# Clock_Generator_REV2.net
KiCad netlist of a schematic drawn in Altium Designer
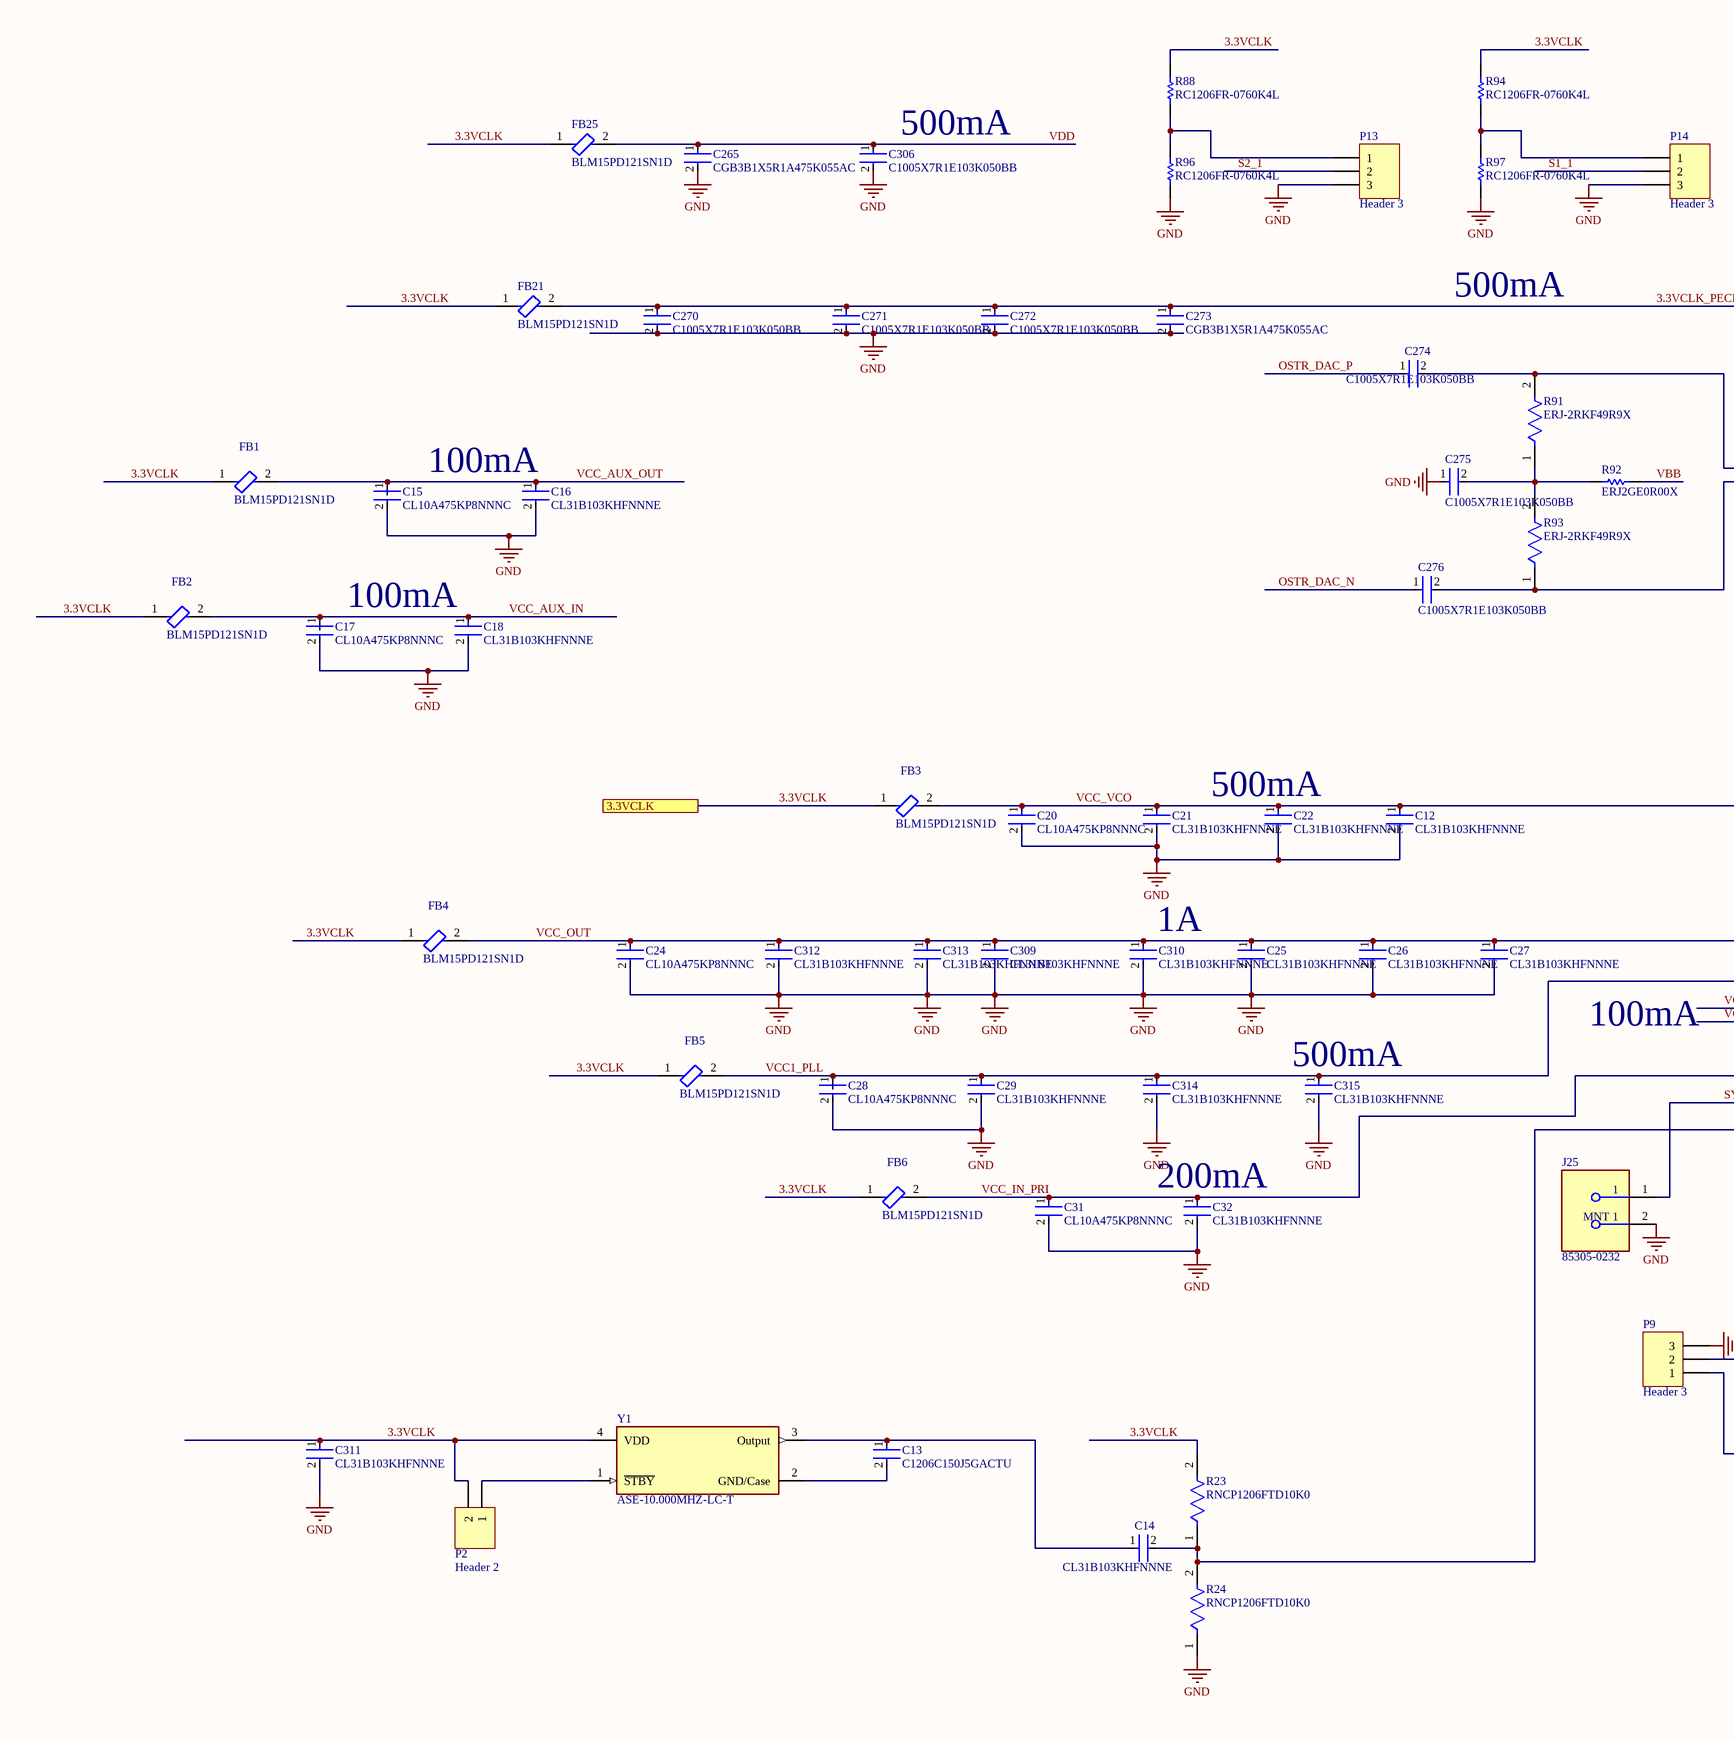
[diagram p0: Clock_Generator_REV2.SchDoc, left]
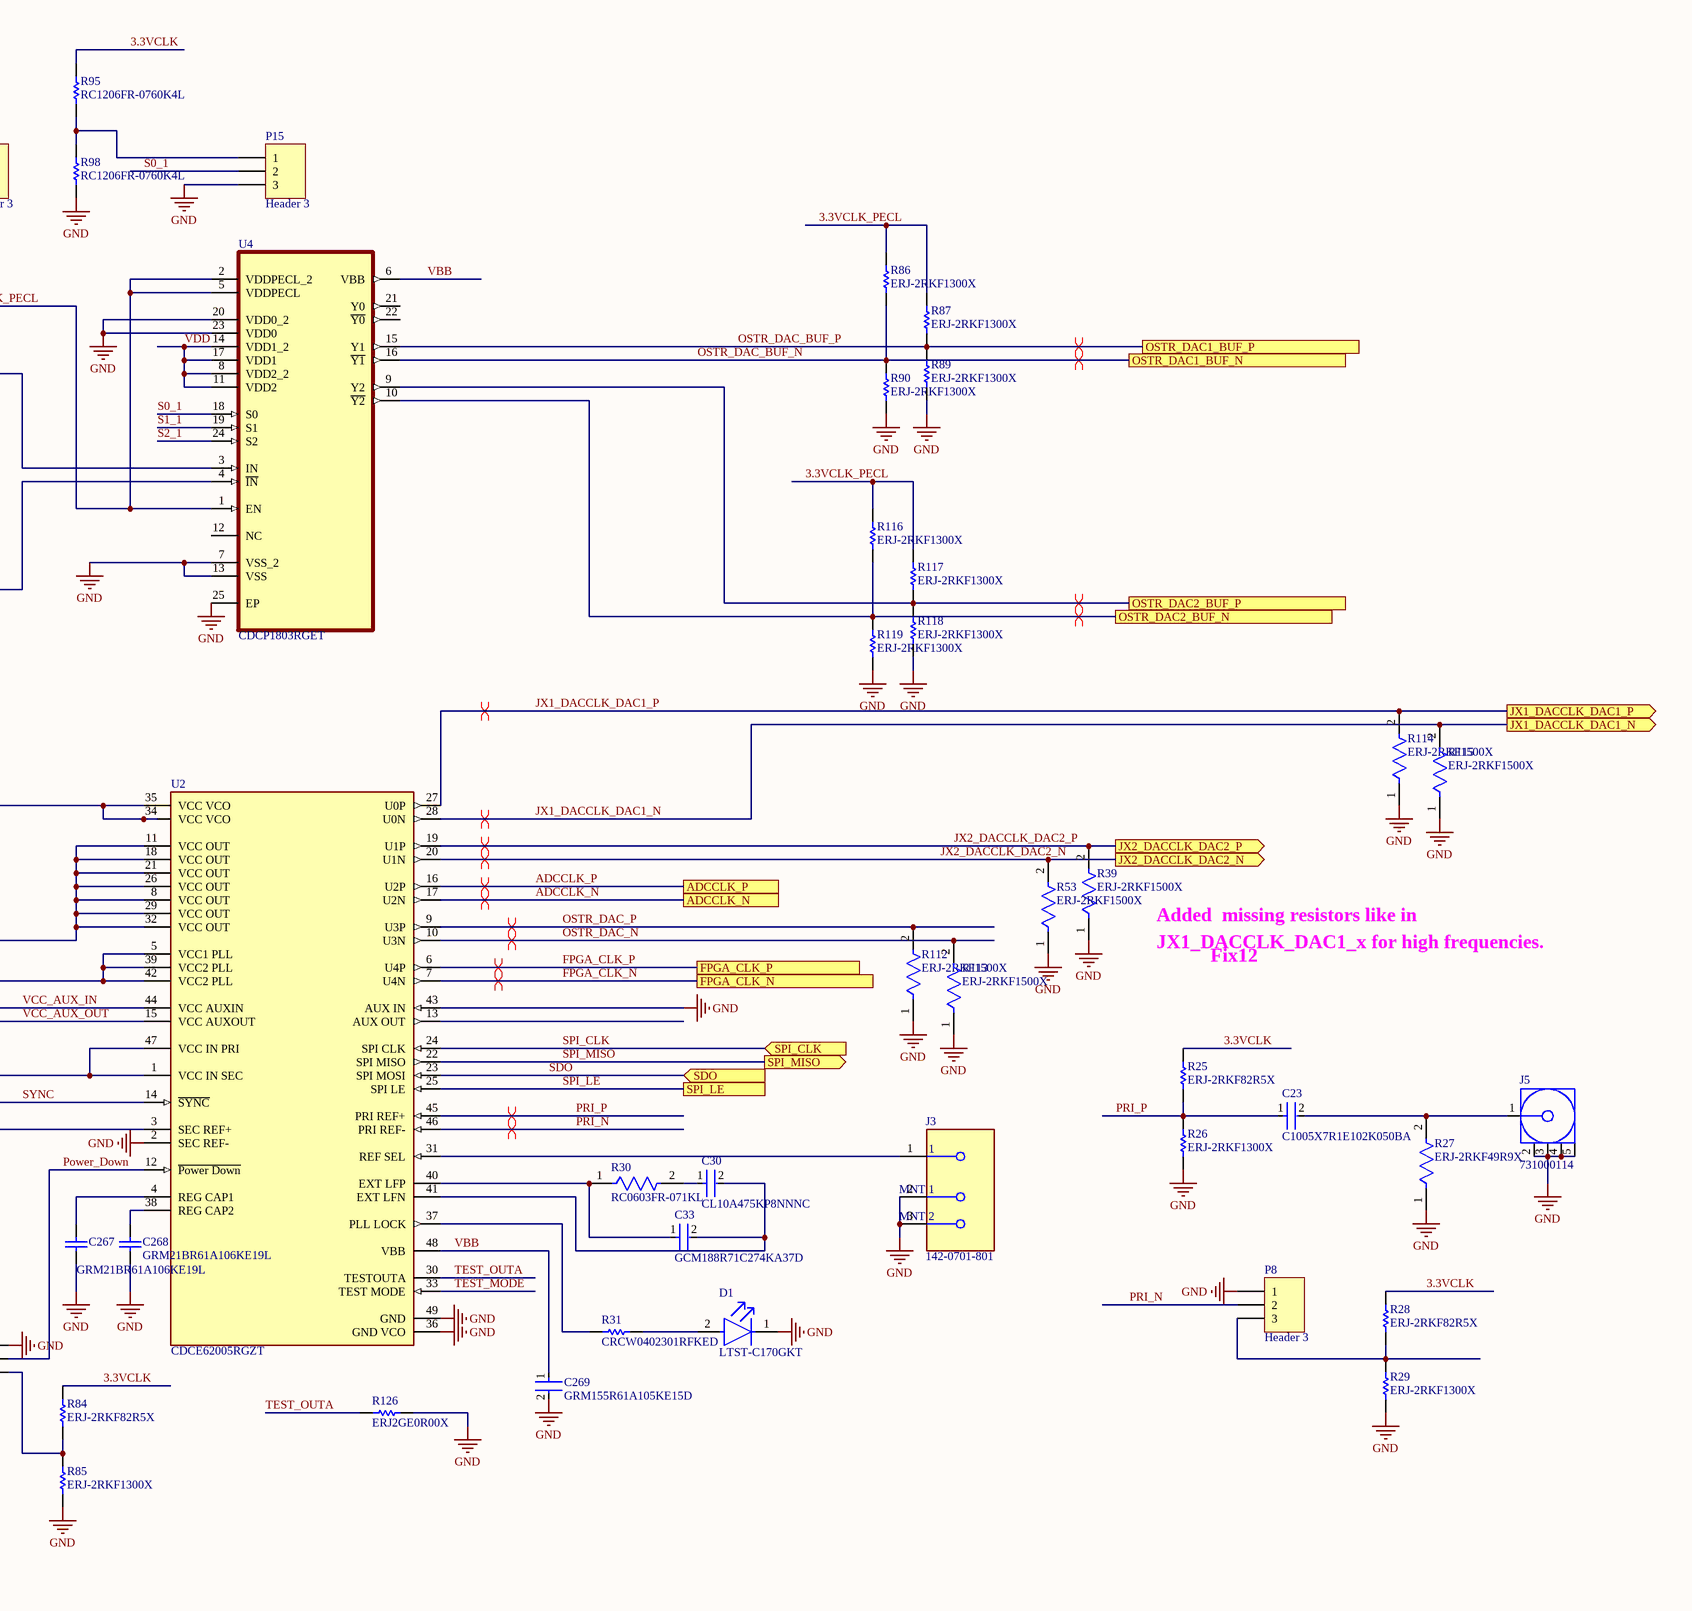
[diagram p1: Clock_Generator_REV2.SchDoc, right]

(export (version "E")
  (design (tool "Eeschema 10.0.6"))
  (components
    (comp (ref "C12")
      (value "CL31B103KHFNNNE")
      (footprint "C1206")
      (description "Cap Ceramic 10nF 630V X7R ±10% SMD 1206 +125°C Embossed T/R")
      (fields (field (name "TOLERANCE") "10%") (field (name "VOLTAGE") "630V"))
      (libsource (lib "DACֹֹ_Sources") (part "b4654b650e69147ec39a6b967a45e02"))
    )
    (comp (ref "C13")
      (value "C1206C150J5GACTU")
      (footprint "C1206")
      (description "1206 C 15pF Ceramic Multilayer Capacitor; 50 VDC; +125degC; C0G Dielec; +/-5%")
      (fields (field (name "TOLERANCE") "0.05") (field (name "MANUFACTURER") "KEMET"))
      (libsource (lib "DACֹֹ_Sources") (part "b4654b650e69147ec39a6b967a45e02"))
    )
    (comp (ref "C14")
      (value "CL31B103KHFNNNE")
      (footprint "C1206")
      (description "Cap Ceramic 10nF 630V X7R ±10% SMD 1206 +125°C Embossed T/R")
      (fields (field (name "TOLERANCE") "10%") (field (name "VOLTAGE") "630V"))
      (libsource (lib "DACֹֹ_Sources") (part "b4654b650e69147ec39a6b967a45e02"))
    )
    (comp (ref "C15")
      (value "CL10A475KP8NNNC")
      (footprint "C0603")
      (description "Cap Ceramic 4.7uF 10V X5R ±10% Pad SMD 0603 +85°C T/R")
      (fields (field (name "TOLERANCE") "10%"))
      (libsource (lib "DACֹֹ_Sources") (part "b4654b650e69147ec39a6b967a45e02"))
    )
    (comp (ref "C16")
      (value "CL31B103KHFNNNE")
      (footprint "C1206")
      (description "Cap Ceramic 10nF 630V X7R ±10% SMD 1206 +125°C Embossed T/R")
      (fields (field (name "TOLERANCE") "10%") (field (name "VOLTAGE") "630V"))
      (libsource (lib "DACֹֹ_Sources") (part "b4654b650e69147ec39a6b967a45e02"))
    )
    (comp (ref "C17")
      (value "CL10A475KP8NNNC")
      (footprint "C0603")
      (description "Cap Ceramic 4.7uF 10V X5R ±10% Pad SMD 0603 +85°C T/R")
      (fields (field (name "TOLERANCE") "10%"))
      (libsource (lib "DACֹֹ_Sources") (part "b4654b650e69147ec39a6b967a45e02"))
    )
    (comp (ref "C18")
      (value "CL31B103KHFNNNE")
      (footprint "C1206")
      (description "Cap Ceramic 10nF 630V X7R ±10% SMD 1206 +125°C Embossed T/R")
      (fields (field (name "TOLERANCE") "10%") (field (name "VOLTAGE") "630V"))
      (libsource (lib "DACֹֹ_Sources") (part "b4654b650e69147ec39a6b967a45e02"))
    )
    (comp (ref "C20")
      (value "CL10A475KP8NNNC")
      (footprint "C0603")
      (description "Cap Ceramic 4.7uF 10V X5R ±10% Pad SMD 0603 +85°C T/R")
      (fields (field (name "TOLERANCE") "10%"))
      (libsource (lib "DACֹֹ_Sources") (part "b4654b650e69147ec39a6b967a45e02"))
    )
    (comp (ref "C21")
      (value "CL31B103KHFNNNE")
      (footprint "C1206")
      (description "Cap Ceramic 10nF 630V X7R ±10% SMD 1206 +125°C Embossed T/R")
      (fields (field (name "TOLERANCE") "10%") (field (name "VOLTAGE") "630V"))
      (libsource (lib "DACֹֹ_Sources") (part "b4654b650e69147ec39a6b967a45e02"))
    )
    (comp (ref "C22")
      (value "CL31B103KHFNNNE")
      (footprint "C1206")
      (description "Cap Ceramic 10nF 630V X7R ±10% SMD 1206 +125°C Embossed T/R")
      (fields (field (name "TOLERANCE") "10%") (field (name "VOLTAGE") "630V"))
      (libsource (lib "DACֹֹ_Sources") (part "b4654b650e69147ec39a6b967a45e02"))
    )
    (comp (ref "C23")
      (value "C1005X7R1E102K050BA")
      (footprint "C0402")
      (description "Multilayer Ceramic Capacitors 1nF ±10% 25V X7R SMD 0402")
      (fields (field (name "TOLERANCE") "10%"))
      (libsource (lib "DACֹֹ_Sources") (part "b4654b650e69147ec39a6b967a45e02"))
    )
    (comp (ref "C24")
      (value "CL10A475KP8NNNC")
      (footprint "C0603")
      (description "Cap Ceramic 4.7uF 10V X5R ±10% Pad SMD 0603 +85°C T/R")
      (fields (field (name "TOLERANCE") "10%"))
      (libsource (lib "DACֹֹ_Sources") (part "b4654b650e69147ec39a6b967a45e02"))
    )
    (comp (ref "C25")
      (value "CL31B103KHFNNNE")
      (footprint "C1206")
      (description "Cap Ceramic 10nF 630V X7R ±10% SMD 1206 +125°C Embossed T/R")
      (fields (field (name "TOLERANCE") "10%") (field (name "VOLTAGE") "630V"))
      (libsource (lib "DACֹֹ_Sources") (part "b4654b650e69147ec39a6b967a45e02"))
    )
    (comp (ref "C26")
      (value "CL31B103KHFNNNE")
      (footprint "C1206")
      (description "Cap Ceramic 10nF 630V X7R ±10% SMD 1206 +125°C Embossed T/R")
      (fields (field (name "TOLERANCE") "10%") (field (name "VOLTAGE") "630V"))
      (libsource (lib "DACֹֹ_Sources") (part "b4654b650e69147ec39a6b967a45e02"))
    )
    (comp (ref "C27")
      (value "CL31B103KHFNNNE")
      (footprint "C1206")
      (description "Cap Ceramic 10nF 630V X7R ±10% SMD 1206 +125°C Embossed T/R")
      (fields (field (name "TOLERANCE") "10%") (field (name "VOLTAGE") "630V"))
      (libsource (lib "DACֹֹ_Sources") (part "b4654b650e69147ec39a6b967a45e02"))
    )
    (comp (ref "C28")
      (value "CL10A475KP8NNNC")
      (footprint "C0603")
      (description "Cap Ceramic 4.7uF 10V X5R ±10% Pad SMD 0603 +85°C T/R")
      (fields (field (name "TOLERANCE") "10%"))
      (libsource (lib "DACֹֹ_Sources") (part "b4654b650e69147ec39a6b967a45e02"))
    )
    (comp (ref "C29")
      (value "CL31B103KHFNNNE")
      (footprint "C1206")
      (description "Cap Ceramic 10nF 630V X7R ±10% SMD 1206 +125°C Embossed T/R")
      (fields (field (name "TOLERANCE") "10%") (field (name "VOLTAGE") "630V"))
      (libsource (lib "DACֹֹ_Sources") (part "b4654b650e69147ec39a6b967a45e02"))
    )
    (comp (ref "C30")
      (value "CL10A475KP8NNNC")
      (footprint "C0603")
      (description "Cap Ceramic 4.7uF 10V X5R ±10% Pad SMD 0603 +85°C T/R")
      (fields (field (name "TOLERANCE") "10%"))
      (libsource (lib "DACֹֹ_Sources") (part "b4654b650e69147ec39a6b967a45e02"))
    )
    (comp (ref "C31")
      (value "CL10A475KP8NNNC")
      (footprint "C0603")
      (description "Cap Ceramic 4.7uF 10V X5R ±10% Pad SMD 0603 +85°C T/R")
      (fields (field (name "TOLERANCE") "10%"))
      (libsource (lib "DACֹֹ_Sources") (part "b4654b650e69147ec39a6b967a45e02"))
    )
    (comp (ref "C32")
      (value "CL31B103KHFNNNE")
      (footprint "C1206")
      (description "Cap Ceramic 10nF 630V X7R ±10% SMD 1206 +125°C Embossed T/R")
      (fields (field (name "TOLERANCE") "10%") (field (name "VOLTAGE") "630V"))
      (libsource (lib "DACֹֹ_Sources") (part "b4654b650e69147ec39a6b967a45e02"))
    )
    (comp (ref "C33")
      (value "GCM188R71C274KA37D")
      (footprint "C0603")
      (description "Ceramic Capacitor for Automotive 270nF  ±10% 16VDC X7R 0603 Paper T/R")
      (fields (field (name "TOLERANCE") "10%"))
      (libsource (lib "DACֹֹ_Sources") (part "02cd4be3c70576c341d710602a673aa"))
    )
    (comp (ref "C265")
      (value "CGB3B1X5R1A475K055AC")
      (footprint "C0603")
      (description "CAP CER 4.7UF 10V X5R 0603")
      (fields (field (name "TOLERANCE") "10%"))
      (libsource (lib "DACֹֹ_Sources") (part "b4654b650e69147ec39a6b967a45e02"))
    )
    (comp (ref "C267")
      (value "GRM21BR61A106KE19L")
      (footprint "C0805")
      (description "CAP, Ceramic, 10 uF, 10%, 10 V, 0805, RoHS, Tape and Reel")
      (fields (field (name "MANUFACTURER") "Murata") (field (name "TOLERANCE") "±10%"))
      (libsource (lib "DACֹֹ_Sources") (part "CAP-NP-2"))
    )
    (comp (ref "C268")
      (value "GRM21BR61A106KE19L")
      (footprint "C0805")
      (description "CAP, Ceramic, 10 uF, 10%, 10 V, 0805, RoHS, Tape and Reel")
      (fields (field (name "MANUFACTURER") "Murata") (field (name "TOLERANCE") "±10%"))
      (libsource (lib "DACֹֹ_Sources") (part "CAP-NP-2"))
    )
    (comp (ref "C269")
      (value "GRM155R61A105KE15D")
      (footprint "C0402")
      (description "CAP CER 1UF 10V X5R 0402")
      (fields
        (field (name "OCTOPART") "https://octopart.com/grm155r61a105ke15d-murata-197442")
        (field (name "MANUFACTURER") "Murata")
      )
      (libsource (lib "DACֹֹ_Sources") (part "02cd4be3c70576c341d710602a673aa"))
    )
    (comp (ref "C270")
      (value "C1005X7R1E103K050BB")
      (footprint "C0402")
      (description "Multilayer Ceramic Capacitors 10nF ±10% 25V X7R SMD 0402")
      (fields (field (name "TOLERANCE") "10%") (field (name "VOLTAGE") "25V"))
      (libsource (lib "DACֹֹ_Sources") (part "b4654b650e69147ec39a6b967a45e02"))
    )
    (comp (ref "C271")
      (value "C1005X7R1E103K050BB")
      (footprint "C0402")
      (description "Multilayer Ceramic Capacitors 10nF ±10% 25V X7R SMD 0402")
      (fields (field (name "TOLERANCE") "10%") (field (name "VOLTAGE") "25V"))
      (libsource (lib "DACֹֹ_Sources") (part "b4654b650e69147ec39a6b967a45e02"))
    )
    (comp (ref "C272")
      (value "C1005X7R1E103K050BB")
      (footprint "C0402")
      (description "Multilayer Ceramic Capacitors 10nF ±10% 25V X7R SMD 0402")
      (fields (field (name "TOLERANCE") "10%") (field (name "VOLTAGE") "25V"))
      (libsource (lib "DACֹֹ_Sources") (part "b4654b650e69147ec39a6b967a45e02"))
    )
    (comp (ref "C273")
      (value "CGB3B1X5R1A475K055AC")
      (footprint "C0603")
      (description "CAP CER 4.7UF 10V X5R 0603")
      (fields (field (name "TOLERANCE") "10%"))
      (libsource (lib "DACֹֹ_Sources") (part "b4654b650e69147ec39a6b967a45e02"))
    )
    (comp (ref "C274")
      (value "C1005X7R1E103K050BB")
      (footprint "C0402")
      (description "Multilayer Ceramic Capacitors 10nF ±10% 25V X7R SMD 0402")
      (fields (field (name "TOLERANCE") "10%") (field (name "VOLTAGE") "25V"))
      (libsource (lib "DACֹֹ_Sources") (part "b4654b650e69147ec39a6b967a45e02"))
    )
    (comp (ref "C275")
      (value "C1005X7R1E103K050BB")
      (footprint "C0402")
      (description "Multilayer Ceramic Capacitors 10nF ±10% 25V X7R SMD 0402")
      (fields (field (name "TOLERANCE") "10%") (field (name "VOLTAGE") "25V"))
      (libsource (lib "DACֹֹ_Sources") (part "b4654b650e69147ec39a6b967a45e02"))
    )
    (comp (ref "C276")
      (value "C1005X7R1E103K050BB")
      (footprint "C0402")
      (description "Multilayer Ceramic Capacitors 10nF ±10% 25V X7R SMD 0402")
      (fields (field (name "TOLERANCE") "10%") (field (name "VOLTAGE") "25V"))
      (libsource (lib "DACֹֹ_Sources") (part "b4654b650e69147ec39a6b967a45e02"))
    )
    (comp (ref "C306")
      (value "C1005X7R1E103K050BB")
      (footprint "C0402")
      (description "Multilayer Ceramic Capacitors 10nF ±10% 25V X7R SMD 0402")
      (fields (field (name "TOLERANCE") "10%") (field (name "VOLTAGE") "25V"))
      (libsource (lib "DACֹֹ_Sources") (part "b4654b650e69147ec39a6b967a45e02"))
    )
    (comp (ref "C309")
      (value "CL31B103KHFNNNE")
      (footprint "C1206")
      (description "Cap Ceramic 10nF 630V X7R ±10% SMD 1206 +125°C Embossed T/R")
      (fields (field (name "TOLERANCE") "10%") (field (name "VOLTAGE") "630V"))
      (libsource (lib "DACֹֹ_Sources") (part "b4654b650e69147ec39a6b967a45e02"))
    )
    (comp (ref "C310")
      (value "CL31B103KHFNNNE")
      (footprint "C1206")
      (description "Cap Ceramic 10nF 630V X7R ±10% SMD 1206 +125°C Embossed T/R")
      (fields (field (name "TOLERANCE") "10%") (field (name "VOLTAGE") "630V"))
      (libsource (lib "DACֹֹ_Sources") (part "b4654b650e69147ec39a6b967a45e02"))
    )
    (comp (ref "C311")
      (value "CL31B103KHFNNNE")
      (footprint "C1206")
      (description "Cap Ceramic 10nF 630V X7R ±10% SMD 1206 +125°C Embossed T/R")
      (fields (field (name "TOLERANCE") "10%") (field (name "VOLTAGE") "630V"))
      (libsource (lib "DACֹֹ_Sources") (part "b4654b650e69147ec39a6b967a45e02"))
    )
    (comp (ref "C312")
      (value "CL31B103KHFNNNE")
      (footprint "C1206")
      (description "Cap Ceramic 10nF 630V X7R ±10% SMD 1206 +125°C Embossed T/R")
      (fields (field (name "TOLERANCE") "10%") (field (name "VOLTAGE") "630V"))
      (libsource (lib "DACֹֹ_Sources") (part "b4654b650e69147ec39a6b967a45e02"))
    )
    (comp (ref "C313")
      (value "CL31B103KHFNNNE")
      (footprint "C1206")
      (description "Cap Ceramic 10nF 630V X7R ±10% SMD 1206 +125°C Embossed T/R")
      (fields (field (name "TOLERANCE") "10%") (field (name "VOLTAGE") "630V"))
      (libsource (lib "DACֹֹ_Sources") (part "b4654b650e69147ec39a6b967a45e02"))
    )
    (comp (ref "C314")
      (value "CL31B103KHFNNNE")
      (footprint "C1206")
      (description "Cap Ceramic 10nF 630V X7R ±10% SMD 1206 +125°C Embossed T/R")
      (fields (field (name "TOLERANCE") "10%") (field (name "VOLTAGE") "630V"))
      (libsource (lib "DACֹֹ_Sources") (part "b4654b650e69147ec39a6b967a45e02"))
    )
    (comp (ref "C315")
      (value "CL31B103KHFNNNE")
      (footprint "C1206")
      (description "Cap Ceramic 10nF 630V X7R ±10% SMD 1206 +125°C Embossed T/R")
      (fields (field (name "TOLERANCE") "10%") (field (name "VOLTAGE") "630V"))
      (libsource (lib "DACֹֹ_Sources") (part "b4654b650e69147ec39a6b967a45e02"))
    )
    (comp (ref "D1")
      (value "LTST-C170GKT")
      (footprint "FP-LTST-C170GKT-MFG")
      (description "LED GREEN CLEAR SMD")
      (fields (field (name "VOLTAGE") "5V"))
      (libsource (lib "DACֹֹ_Sources") (part "8706943c75ba83719d021d2fdc84c58"))
    )
    (comp (ref "FB1")
      (value "BLM15PD121SN1D")
      (footprint "BLM15")
      (description "Chip Ferrite Bead, 0402, 120Ω @ 100MHz, 0.09Ω, 25%, 1.3A")
      (fields (field (name "TOLERANCE") "25%"))
      (libsource (lib "DACֹֹ_Sources") (part "5f30dd21d616792df468990f7003faa"))
    )
    (comp (ref "FB2")
      (value "BLM15PD121SN1D")
      (footprint "BLM15")
      (description "Chip Ferrite Bead, 0402, 120Ω @ 100MHz, 0.09Ω, 25%, 1.3A")
      (fields (field (name "TOLERANCE") "25%"))
      (libsource (lib "DACֹֹ_Sources") (part "5f30dd21d616792df468990f7003faa"))
    )
    (comp (ref "FB3")
      (value "BLM15PD121SN1D")
      (footprint "BLM15")
      (description "Chip Ferrite Bead, 0402, 120Ω @ 100MHz, 0.09Ω, 25%, 1.3A")
      (fields (field (name "TOLERANCE") "25%"))
      (libsource (lib "DACֹֹ_Sources") (part "5f30dd21d616792df468990f7003faa"))
    )
    (comp (ref "FB4")
      (value "BLM15PD121SN1D")
      (footprint "BLM15")
      (description "Chip Ferrite Bead, 0402, 120Ω @ 100MHz, 0.09Ω, 25%, 1.3A")
      (fields (field (name "TOLERANCE") "25%"))
      (libsource (lib "DACֹֹ_Sources") (part "5f30dd21d616792df468990f7003faa"))
    )
    (comp (ref "FB5")
      (value "BLM15PD121SN1D")
      (footprint "BLM15")
      (description "Chip Ferrite Bead, 0402, 120Ω @ 100MHz, 0.09Ω, 25%, 1.3A")
      (fields (field (name "TOLERANCE") "25%"))
      (libsource (lib "DACֹֹ_Sources") (part "5f30dd21d616792df468990f7003faa"))
    )
    (comp (ref "FB6")
      (value "BLM15PD121SN1D")
      (footprint "BLM15")
      (description "Chip Ferrite Bead, 0402, 120Ω @ 100MHz, 0.09Ω, 25%, 1.3A")
      (fields (field (name "TOLERANCE") "25%"))
      (libsource (lib "DACֹֹ_Sources") (part "5f30dd21d616792df468990f7003faa"))
    )
    (comp (ref "FB21")
      (value "BLM15PD121SN1D")
      (footprint "BLM15")
      (description "Chip Ferrite Bead, 0402, 120Ω @ 100MHz, 0.09Ω, 25%, 1.3A")
      (fields (field (name "TOLERANCE") "25%"))
      (libsource (lib "DACֹֹ_Sources") (part "5f30dd21d616792df468990f7003faa"))
    )
    (comp (ref "FB25")
      (value "BLM15PD121SN1D")
      (footprint "BLM15")
      (description "Chip Ferrite Bead, 0402, 120Ω @ 100MHz, 0.09Ω, 25%, 1.3A")
      (fields (field (name "TOLERANCE") "25%"))
      (libsource (lib "DACֹֹ_Sources") (part "5f30dd21d616792df468990f7003faa"))
    )
    (comp (ref "J3")
      (value "142-0701-801")
      (footprint "FP-142-0701-801-MFG")
      (description "CONN SMA JACK STR 50OHM EDGE MNT")
      (libsource (lib "DACֹֹ_Sources") (part "89929399afe843c8b6880c6cbd0f99a"))
    )
    (comp (ref "J5")
      (value "731000114")
      (footprint "MOLX-731000114_V")
      (description "SMA Right-Angle PCB Jack Receptacle, Brass Body, Gold Plated, 50 Ohm, 5-Pin THD, RoHS, Tray")
      (fields (field (name "MANUFACTURER") "Molex"))
      (libsource (lib "DACֹֹ_Sources") (part "CN-S-4F-RF5"))
    )
    (comp (ref "J25")
      (value "85305-0232")
      (footprint "FP-85305-0232-MFG")
      (description "CONN SMP PLUG STR 50 OHM SMD")
      (libsource (lib "DACֹֹ_Sources") (part "d2a53f3a980517e545f22a6fb6569cc"))
    )
    (comp (ref "P2")
      (value "Header 2")
      (footprint "HEADER_2X1")
      (description "Header, 2-Pin")
      (fields (field (name "PUBLISHER") "Altium Limited"))
      (libsource (lib "DACֹֹ_Sources") (part "Header 2"))
    )
    (comp (ref "P8")
      (value "Header 3")
      (footprint "HEADER_3X1")
      (description "Header, 3-Pin")
      (fields (field (name "PUBLISHER") "Altium Limited"))
      (libsource (lib "") (part "Header 3_1"))
    )
    (comp (ref "P9")
      (value "Header 3")
      (footprint "HEADER_3X1")
      (description "Header, 3-Pin")
      (fields (field (name "PUBLISHER") "Altium Limited"))
      (libsource (lib "DACֹֹ_Sources") (part "Header 3"))
    )
    (comp (ref "P13")
      (value "Header 3")
      (footprint "HEADER_3X1")
      (description "Header, 3-Pin")
      (fields (field (name "PUBLISHER") "Altium Limited"))
      (libsource (lib "") (part "Header 3_1"))
    )
    (comp (ref "P14")
      (value "Header 3")
      (footprint "HEADER_3X1")
      (description "Header, 3-Pin")
      (fields (field (name "PUBLISHER") "Altium Limited"))
      (libsource (lib "") (part "Header 3_1"))
    )
    (comp (ref "P15")
      (value "Header 3")
      (footprint "HEADER_3X1")
      (description "Header, 3-Pin")
      (fields (field (name "PUBLISHER") "Altium Limited"))
      (libsource (lib "") (part "Header 3_1"))
    )
    (comp (ref "R23")
      (value "RNCP1206FTD10K0")
      (footprint "R1206")
      (description "10kΩ ±1% 0.5W 1206 High Power Anti-Sulfur Thin Film Chip Resistor")
      (fields (field (name "TOLERANCE") "1%"))
      (libsource (lib "DACֹֹ_Sources") (part "1029c3af85768c4190bb7ad29bc67b5"))
    )
    (comp (ref "R24")
      (value "RNCP1206FTD10K0")
      (footprint "R1206")
      (description "10kΩ ±1% 0.5W 1206 High Power Anti-Sulfur Thin Film Chip Resistor")
      (fields (field (name "TOLERANCE") "1%"))
      (libsource (lib "DACֹֹ_Sources") (part "1029c3af85768c4190bb7ad29bc67b5"))
    )
    (comp (ref "R25")
      (value "ERJ-2RKF82R5X")
      (footprint "R0402")
      (fields (field (name "MANUFACTURER") "Panasonic"))
      (libsource (lib "DACֹֹ_Sources") (part "RES"))
    )
    (comp (ref "R26")
      (value "ERJ-2RKF1300X")
      (footprint "R0402")
      (fields (field (name "MANUFACTURER") "Panasonic"))
      (libsource (lib "DACֹֹ_Sources") (part "RES"))
    )
    (comp (ref "R27")
      (value "ERJ-2RKF49R9X")
      (footprint "R0402")
      (description "RES SMD 49.9 OHM 1% 1/10W 0402")
      (fields (field (name "TOLERANCE") "1%"))
      (libsource (lib "DACֹֹ_Sources") (part "8db39607336c341a927600551d01821"))
    )
    (comp (ref "R28")
      (value "ERJ-2RKF82R5X")
      (footprint "R0402")
      (fields (field (name "MANUFACTURER") "Panasonic"))
      (libsource (lib "DACֹֹ_Sources") (part "RES"))
    )
    (comp (ref "R29")
      (value "ERJ-2RKF1300X")
      (footprint "R0402")
      (fields (field (name "MANUFACTURER") "Panasonic"))
      (libsource (lib "DACֹֹ_Sources") (part "RES"))
    )
    (comp (ref "R30")
      (value "RC0603FR-071KL")
      (footprint "R0603")
      (description "RES 1K OHM 1% 1/10W 0603")
      (fields (field (name "TOLERANCE") "1%"))
      (libsource (lib "DACֹֹ_Sources") (part "1029c3af85768c4190bb7ad29bc67b5"))
    )
    (comp (ref "R31")
      (value "CRCW0402301RFKED")
      (footprint "R0402")
      (fields (field (name "MANUFACTURER") "Vishay Dale"))
      (libsource (lib "DACֹֹ_Sources") (part "RES"))
    )
    (comp (ref "R39")
      (value "ERJ-2RKF1500X")
      (footprint "R0402")
      (description "RES SMD 150 OHM 1% 1/10W 0402")
      (fields (field (name "TOLERANCE") "1%"))
      (libsource (lib "DACֹֹ_Sources") (part "1029c3af85768c4190bb7ad29bc67b5"))
    )
    (comp (ref "R53")
      (value "ERJ-2RKF1500X")
      (footprint "R0402")
      (description "RES SMD 150 OHM 1% 1/10W 0402")
      (fields (field (name "TOLERANCE") "1%"))
      (libsource (lib "DACֹֹ_Sources") (part "1029c3af85768c4190bb7ad29bc67b5"))
    )
    (comp (ref "R84")
      (value "ERJ-2RKF82R5X")
      (footprint "R0402")
      (fields (field (name "MANUFACTURER") "Panasonic"))
      (libsource (lib "DACֹֹ_Sources") (part "RES"))
    )
    (comp (ref "R85")
      (value "ERJ-2RKF1300X")
      (footprint "R0402")
      (fields (field (name "MANUFACTURER") "Panasonic"))
      (libsource (lib "DACֹֹ_Sources") (part "RES"))
    )
    (comp (ref "R86")
      (value "ERJ-2RKF1300X")
      (footprint "R0402")
      (fields (field (name "MANUFACTURER") "Panasonic"))
      (libsource (lib "DACֹֹ_Sources") (part "RES"))
    )
    (comp (ref "R87")
      (value "ERJ-2RKF1300X")
      (footprint "R0402")
      (fields (field (name "MANUFACTURER") "Panasonic"))
      (libsource (lib "DACֹֹ_Sources") (part "RES"))
    )
    (comp (ref "R88")
      (value "RC1206FR-0760K4L")
      (footprint "R1206")
      (fields (field (name "MANUFACTURER") "Yageo"))
      (libsource (lib "DACֹֹ_Sources") (part "RES"))
    )
    (comp (ref "R89")
      (value "ERJ-2RKF1300X")
      (footprint "R0402")
      (fields (field (name "MANUFACTURER") "Panasonic"))
      (libsource (lib "DACֹֹ_Sources") (part "RES"))
    )
    (comp (ref "R90")
      (value "ERJ-2RKF1300X")
      (footprint "R0402")
      (fields (field (name "MANUFACTURER") "Panasonic"))
      (libsource (lib "DACֹֹ_Sources") (part "RES"))
    )
    (comp (ref "R91")
      (value "ERJ-2RKF49R9X")
      (footprint "R0402")
      (description "RES SMD 49.9 OHM 1% 1/10W 0402")
      (fields (field (name "TOLERANCE") "1%"))
      (libsource (lib "DACֹֹ_Sources") (part "8db39607336c341a927600551d01821"))
    )
    (comp (ref "R92")
      (value "ERJ2GE0R00X")
      (footprint "R0402")
      (description "Chip Resistor, 0 Ohm, 0.1 W, -55 to 155 degC, 0402 (1005 Metric), RoHS, Tape and Reel")
      (fields (field (name "MANUFACTURER") "Panasonic") (field (name "TOLERANCE") "5%"))
      (libsource (lib "DACֹֹ_Sources") (part "RES-2"))
    )
    (comp (ref "R93")
      (value "ERJ-2RKF49R9X")
      (footprint "R0402")
      (description "RES SMD 49.9 OHM 1% 1/10W 0402")
      (fields (field (name "TOLERANCE") "1%"))
      (libsource (lib "DACֹֹ_Sources") (part "8db39607336c341a927600551d01821"))
    )
    (comp (ref "R94")
      (value "RC1206FR-0760K4L")
      (footprint "R1206")
      (fields (field (name "MANUFACTURER") "Yageo"))
      (libsource (lib "DACֹֹ_Sources") (part "RES"))
    )
    (comp (ref "R95")
      (value "RC1206FR-0760K4L")
      (footprint "R1206")
      (fields (field (name "MANUFACTURER") "Yageo"))
      (libsource (lib "DACֹֹ_Sources") (part "RES"))
    )
    (comp (ref "R96")
      (value "RC1206FR-0760K4L")
      (footprint "R1206")
      (fields (field (name "MANUFACTURER") "Yageo"))
      (libsource (lib "DACֹֹ_Sources") (part "RES"))
    )
    (comp (ref "R97")
      (value "RC1206FR-0760K4L")
      (footprint "R1206")
      (fields (field (name "MANUFACTURER") "Yageo"))
      (libsource (lib "DACֹֹ_Sources") (part "RES"))
    )
    (comp (ref "R98")
      (value "RC1206FR-0760K4L")
      (footprint "R1206")
      (fields (field (name "MANUFACTURER") "Yageo"))
      (libsource (lib "DACֹֹ_Sources") (part "RES"))
    )
    (comp (ref "R112")
      (value "ERJ-2RKF1500X")
      (footprint "R0402")
      (description "RES SMD 150 OHM 1% 1/10W 0402")
      (fields (field (name "TOLERANCE") "1%"))
      (libsource (lib "DACֹֹ_Sources") (part "1029c3af85768c4190bb7ad29bc67b5"))
    )
    (comp (ref "R113")
      (value "ERJ-2RKF1500X")
      (footprint "R0402")
      (description "RES SMD 150 OHM 1% 1/10W 0402")
      (fields (field (name "TOLERANCE") "1%"))
      (libsource (lib "DACֹֹ_Sources") (part "1029c3af85768c4190bb7ad29bc67b5"))
    )
    (comp (ref "R114")
      (value "ERJ-2RKF1500X")
      (footprint "R0402")
      (description "RES SMD 150 OHM 1% 1/10W 0402")
      (fields (field (name "TOLERANCE") "1%"))
      (libsource (lib "DACֹֹ_Sources") (part "1029c3af85768c4190bb7ad29bc67b5"))
    )
    (comp (ref "R115")
      (value "ERJ-2RKF1500X")
      (footprint "R0402")
      (description "RES SMD 150 OHM 1% 1/10W 0402")
      (fields (field (name "TOLERANCE") "1%"))
      (libsource (lib "DACֹֹ_Sources") (part "1029c3af85768c4190bb7ad29bc67b5"))
    )
    (comp (ref "R116")
      (value "ERJ-2RKF1300X")
      (footprint "R0402")
      (fields (field (name "MANUFACTURER") "Panasonic"))
      (libsource (lib "DACֹֹ_Sources") (part "RES"))
    )
    (comp (ref "R117")
      (value "ERJ-2RKF1300X")
      (footprint "R0402")
      (fields (field (name "MANUFACTURER") "Panasonic"))
      (libsource (lib "DACֹֹ_Sources") (part "RES"))
    )
    (comp (ref "R118")
      (value "ERJ-2RKF1300X")
      (footprint "R0402")
      (fields (field (name "MANUFACTURER") "Panasonic"))
      (libsource (lib "DACֹֹ_Sources") (part "RES"))
    )
    (comp (ref "R119")
      (value "ERJ-2RKF1300X")
      (footprint "R0402")
      (fields (field (name "MANUFACTURER") "Panasonic"))
      (libsource (lib "DACֹֹ_Sources") (part "RES"))
    )
    (comp (ref "R126")
      (value "ERJ2GE0R00X")
      (footprint "R0402")
      (description "Chip Resistor, 0 Ohm, 0.1 W, -55 to 155 degC, 0402 (1005 Metric), RoHS, Tape and Reel")
      (fields (field (name "MANUFACTURER") "Panasonic") (field (name "TOLERANCE") "5%"))
      (libsource (lib "DACֹֹ_Sources") (part "RES-2"))
    )
    (comp (ref "U2")
      (value "CDCE62005RGZT")
      (footprint "FP-RGZ0048D-IPC_A")
      (description "IC CLK SYNTH/JITTER CLEANR 48QFN")
      (libsource (lib "DACֹֹ_Sources") (part "79e6de338fe35b6fdc3d186d6aa1691"))
    )
    (comp (ref "U4")
      (value "CDCP1803RGET")
      (footprint "QFN25")
      (description "1:3 LVPECL clock buffer with programable divider")
      (fields (field (name "MF") "Texas Instruments"))
      (libsource (lib "DACֹֹ_Sources") (part "CDCP1803RGET"))
    )
    (comp (ref "Y1")
      (value "ASE-10.000MHZ-LC-T")
      (footprint "ASE")
      (description "XTAL Oscillator 10MHz ±50ppm CMOS 3.3V 4-SMD 3.2mm x 2.5mm")
      (libsource (lib "DACֹֹ_Sources") (part "61a724e6190563596ac712fef61ad37"))
    )
  )
  (nets
    (net (code "1") (name "/3.3VCLK") (class "Default")
      (node (ref "C311") (pin "1") (pinfunction "1_1") (pintype "passive"))
      (node (ref "FB1") (pin "1") (pinfunction "1_1") (pintype "passive"))
      (node (ref "FB2") (pin "1") (pinfunction "1_1") (pintype "passive"))
      (node (ref "FB21") (pin "1") (pinfunction "1_1") (pintype "passive"))
      (node (ref "FB25") (pin "1") (pinfunction "1_1") (pintype "passive"))
      (node (ref "FB3") (pin "1") (pinfunction "1_1") (pintype "passive"))
      (node (ref "FB4") (pin "1") (pinfunction "1_1") (pintype "passive"))
      (node (ref "FB5") (pin "1") (pinfunction "1_1") (pintype "passive"))
      (node (ref "FB6") (pin "1") (pinfunction "1_1") (pintype "passive"))
      (node (ref "P2") (pin "2") (pinfunction "2_2") (pintype "passive"))
      (node (ref "R23") (pin "2") (pinfunction "2_2") (pintype "passive"))
      (node (ref "R25") (pin "2") (pinfunction "2_2") (pintype "passive"))
      (node (ref "R28") (pin "2") (pinfunction "2_2") (pintype "passive"))
      (node (ref "R84") (pin "2") (pinfunction "2_2") (pintype "passive"))
      (node (ref "R88") (pin "2") (pinfunction "2_2") (pintype "passive"))
      (node (ref "R94") (pin "2") (pinfunction "2_2") (pintype "passive"))
      (node (ref "R95") (pin "2") (pinfunction "2_2") (pintype "passive"))
      (node (ref "Y1") (pin "4") (pinfunction "VDD_4") (pintype "power_in"))
    )
    (net (code "2") (name "/3.3VCLK_PECL") (class "Default")
      (node (ref "C270") (pin "1") (pinfunction "1_1") (pintype "passive"))
      (node (ref "C271") (pin "1") (pinfunction "1_1") (pintype "passive"))
      (node (ref "C272") (pin "1") (pinfunction "1_1") (pintype "passive"))
      (node (ref "C273") (pin "1") (pinfunction "1_1") (pintype "passive"))
      (node (ref "FB21") (pin "2") (pinfunction "2_2") (pintype "passive"))
      (node (ref "R116") (pin "2") (pinfunction "2_2") (pintype "passive"))
      (node (ref "R117") (pin "2") (pinfunction "2_2") (pintype "passive"))
      (node (ref "R86") (pin "2") (pinfunction "2_2") (pintype "passive"))
      (node (ref "R87") (pin "2") (pinfunction "2_2") (pintype "passive"))
      (node (ref "U4") (pin "1") (pinfunction "EN_1") (pintype "input"))
      (node (ref "U4") (pin "2") (pinfunction "VDDPECL_2_2") (pintype "power_in"))
      (node (ref "U4") (pin "5") (pinfunction "VDDPECL_5") (pintype "power_in"))
    )
    (net (code "3") (name "/ADCCLK_N") (class "Default")
      (node (ref "U2") (pin "17") (pinfunction "U2N_17") (pintype "output"))
    )
    (net (code "4") (name "/ADCCLK_P") (class "Default")
      (node (ref "U2") (pin "16") (pinfunction "U2P_16") (pintype "output"))
    )
    (net (code "5") (name "/FPGA_CLK_N") (class "Default")
      (node (ref "U2") (pin "7") (pinfunction "U4N_7") (pintype "output"))
    )
    (net (code "6") (name "/FPGA_CLK_P") (class "Default")
      (node (ref "U2") (pin "6") (pinfunction "U4P_6") (pintype "output"))
    )
    (net (code "7") (name "/JX1_DACCLK_DAC1_N") (class "Default")
      (node (ref "R115") (pin "2") (pinfunction "2_2") (pintype "passive"))
      (node (ref "U2") (pin "28") (pinfunction "U0N_28") (pintype "output"))
    )
    (net (code "8") (name "/JX1_DACCLK_DAC1_P") (class "Default")
      (node (ref "R114") (pin "2") (pinfunction "2_2") (pintype "passive"))
      (node (ref "U2") (pin "27") (pinfunction "U0P_27") (pintype "output"))
    )
    (net (code "9") (name "/JX2_DACCLK_DAC2_N") (class "Default")
      (node (ref "R53") (pin "2") (pinfunction "2_2") (pintype "passive"))
      (node (ref "U2") (pin "20") (pinfunction "U1N_20") (pintype "output"))
    )
    (net (code "10") (name "/JX2_DACCLK_DAC2_P") (class "Default")
      (node (ref "R39") (pin "2") (pinfunction "2_2") (pintype "passive"))
      (node (ref "U2") (pin "19") (pinfunction "U1P_19") (pintype "output"))
    )
    (net (code "11") (name "/OSTR_DAC2_BUF_N") (class "Default")
      (node (ref "R116") (pin "1") (pinfunction "1_1") (pintype "passive"))
      (node (ref "R119") (pin "2") (pinfunction "2_2") (pintype "passive"))
      (node (ref "U4") (pin "10") (pinfunction "~{Y2}_10") (pintype "output"))
    )
    (net (code "12") (name "/OSTR_DAC2_BUF_P") (class "Default")
      (node (ref "R117") (pin "1") (pinfunction "1_1") (pintype "passive"))
      (node (ref "R118") (pin "2") (pinfunction "2_2") (pintype "passive"))
      (node (ref "U4") (pin "9") (pinfunction "Y2_9") (pintype "output"))
    )
    (net (code "13") (name "/OSTR_DAC_BUF_N") (class "Default")
      (node (ref "R86") (pin "1") (pinfunction "1_1") (pintype "passive"))
      (node (ref "R90") (pin "2") (pinfunction "2_2") (pintype "passive"))
      (node (ref "U4") (pin "16") (pinfunction "~{Y1}_16") (pintype "output"))
    )
    (net (code "14") (name "/OSTR_DAC_BUF_P") (class "Default")
      (node (ref "R87") (pin "1") (pinfunction "1_1") (pintype "passive"))
      (node (ref "R89") (pin "2") (pinfunction "2_2") (pintype "passive"))
      (node (ref "U4") (pin "15") (pinfunction "Y1_15") (pintype "output"))
    )
    (net (code "15") (name "/OSTR_DAC_N") (class "Default")
      (node (ref "C276") (pin "1") (pinfunction "1_1") (pintype "passive"))
      (node (ref "R113") (pin "2") (pinfunction "2_2") (pintype "passive"))
      (node (ref "U2") (pin "10") (pinfunction "U3N_10") (pintype "output"))
    )
    (net (code "16") (name "/OSTR_DAC_P") (class "Default")
      (node (ref "C274") (pin "1") (pinfunction "1_1") (pintype "passive"))
      (node (ref "R112") (pin "2") (pinfunction "2_2") (pintype "passive"))
      (node (ref "U2") (pin "9") (pinfunction "U3P_9") (pintype "output"))
    )
    (net (code "17") (name "/PRI_N") (class "Default")
      (node (ref "P8") (pin "2") (pinfunction "2_2") (pintype "passive"))
      (node (ref "U2") (pin "46") (pinfunction "PRI_REF-_46") (pintype "input"))
    )
    (net (code "18") (name "/PRI_P") (class "Default")
      (node (ref "C23") (pin "1") (pinfunction "1_1") (pintype "passive"))
      (node (ref "R25") (pin "1") (pinfunction "1_1") (pintype "passive"))
      (node (ref "R26") (pin "2") (pinfunction "2_2") (pintype "passive"))
      (node (ref "U2") (pin "45") (pinfunction "PRI_REF+_45") (pintype "input"))
    )
    (net (code "19") (name "/Power_Down") (class "Default")
      (node (ref "P9") (pin "2") (pinfunction "2_2") (pintype "passive"))
      (node (ref "U2") (pin "12") (pinfunction "~{Power_Down}_12") (pintype "input"))
    )
    (net (code "20") (name "/S0_1") (class "Default")
      (node (ref "P15") (pin "2") (pinfunction "2_2") (pintype "passive"))
      (node (ref "U4") (pin "18") (pinfunction "S0_18") (pintype "input"))
    )
    (net (code "21") (name "/S1_1") (class "Default")
      (node (ref "P14") (pin "2") (pinfunction "2_2") (pintype "passive"))
      (node (ref "U4") (pin "19") (pinfunction "S1_19") (pintype "input"))
    )
    (net (code "22") (name "/S2_1") (class "Default")
      (node (ref "P13") (pin "2") (pinfunction "2_2") (pintype "passive"))
      (node (ref "U4") (pin "24") (pinfunction "S2_24") (pintype "input"))
    )
    (net (code "23") (name "/SDO") (class "Default")
      (node (ref "U2") (pin "23") (pinfunction "SPI_MOSI_23") (pintype "input"))
    )
    (net (code "24") (name "/SPI_CLK") (class "Default")
      (node (ref "U2") (pin "24") (pinfunction "SPI_CLK_24") (pintype "input"))
    )
    (net (code "25") (name "/SPI_LE") (class "Default")
      (node (ref "U2") (pin "25") (pinfunction "SPI_LE_25") (pintype "input"))
    )
    (net (code "26") (name "/SPI_MISO") (class "Default")
      (node (ref "U2") (pin "22") (pinfunction "SPI_MISO_22") (pintype "output"))
    )
    (net (code "27") (name "/SYNC") (class "Default")
      (node (ref "J25") (pin "1") (pinfunction "1_1") (pintype "passive"))
      (node (ref "U2") (pin "14") (pinfunction "~{SYNC}_14") (pintype "input"))
    )
    (net (code "28") (name "/TEST_MODE") (class "Default")
      (node (ref "U2") (pin "33") (pinfunction "TEST_MODE_33") (pintype "input"))
    )
    (net (code "29") (name "/TEST_OUTA") (class "Default")
      (node (ref "R126") (pin "1") (pinfunction "1_1") (pintype "passive"))
      (node (ref "U2") (pin "30") (pinfunction "TESTOUTA_30") (pintype "passive"))
    )
    (net (code "30") (name "/VBB") (class "Default")
      (node (ref "C269") (pin "1") (pinfunction "1_1") (pintype "passive"))
      (node (ref "R92") (pin "2") (pinfunction "2_2") (pintype "passive"))
      (node (ref "U2") (pin "48") (pinfunction "VBB_48") (pintype "passive"))
      (node (ref "U4") (pin "6") (pinfunction "VBB_6") (pintype "output"))
    )
    (net (code "31") (name "/VCC1_PLL") (class "Default")
      (node (ref "C28") (pin "1") (pinfunction "1_1") (pintype "passive"))
      (node (ref "C29") (pin "1") (pinfunction "1_1") (pintype "passive"))
      (node (ref "C314") (pin "1") (pinfunction "1_1") (pintype "passive"))
      (node (ref "C315") (pin "1") (pinfunction "1_1") (pintype "passive"))
      (node (ref "FB5") (pin "2") (pinfunction "2_2") (pintype "passive"))
      (node (ref "U2") (pin "39") (pinfunction "VCC2_PLL_39") (pintype "power_in"))
      (node (ref "U2") (pin "42") (pinfunction "VCC2_PLL_42") (pintype "power_in"))
      (node (ref "U2") (pin "5") (pinfunction "VCC1_PLL_5") (pintype "power_in"))
    )
    (net (code "32") (name "/VCC_AUX_IN") (class "Default")
      (node (ref "C17") (pin "1") (pinfunction "1_1") (pintype "passive"))
      (node (ref "C18") (pin "1") (pinfunction "1_1") (pintype "passive"))
      (node (ref "FB2") (pin "2") (pinfunction "2_2") (pintype "passive"))
      (node (ref "U2") (pin "44") (pinfunction "VCC_AUXIN_44") (pintype "power_in"))
    )
    (net (code "33") (name "/VCC_AUX_OUT") (class "Default")
      (node (ref "C15") (pin "1") (pinfunction "1_1") (pintype "passive"))
      (node (ref "C16") (pin "1") (pinfunction "1_1") (pintype "passive"))
      (node (ref "FB1") (pin "2") (pinfunction "2_2") (pintype "passive"))
      (node (ref "U2") (pin "15") (pinfunction "VCC_AUXOUT_15") (pintype "power_in"))
    )
    (net (code "34") (name "/VCC_IN_PRI") (class "Default")
      (node (ref "C31") (pin "1") (pinfunction "1_1") (pintype "passive"))
      (node (ref "C32") (pin "1") (pinfunction "1_1") (pintype "passive"))
      (node (ref "FB6") (pin "2") (pinfunction "2_2") (pintype "passive"))
      (node (ref "U2") (pin "1") (pinfunction "VCC_IN_SEC_1") (pintype "power_in"))
      (node (ref "U2") (pin "47") (pinfunction "VCC_IN_PRI_47") (pintype "power_in"))
    )
    (net (code "35") (name "/VCC_OUT") (class "Default")
      (node (ref "C24") (pin "1") (pinfunction "1_1") (pintype "passive"))
      (node (ref "C25") (pin "1") (pinfunction "1_1") (pintype "passive"))
      (node (ref "C26") (pin "1") (pinfunction "1_1") (pintype "passive"))
      (node (ref "C27") (pin "1") (pinfunction "1_1") (pintype "passive"))
      (node (ref "C309") (pin "1") (pinfunction "1_1") (pintype "passive"))
      (node (ref "C310") (pin "1") (pinfunction "1_1") (pintype "passive"))
      (node (ref "C312") (pin "1") (pinfunction "1_1") (pintype "passive"))
      (node (ref "C313") (pin "1") (pinfunction "1_1") (pintype "passive"))
      (node (ref "FB4") (pin "2") (pinfunction "2_2") (pintype "passive"))
      (node (ref "U2") (pin "11") (pinfunction "VCC_OUT_11") (pintype "power_in"))
      (node (ref "U2") (pin "18") (pinfunction "VCC_OUT_18") (pintype "power_in"))
      (node (ref "U2") (pin "21") (pinfunction "VCC_OUT_21") (pintype "power_in"))
      (node (ref "U2") (pin "26") (pinfunction "VCC_OUT_26") (pintype "power_in"))
      (node (ref "U2") (pin "29") (pinfunction "VCC_OUT_29") (pintype "power_in"))
      (node (ref "U2") (pin "32") (pinfunction "VCC_OUT_32") (pintype "power_in"))
      (node (ref "U2") (pin "8") (pinfunction "VCC_OUT_8") (pintype "power_in"))
    )
    (net (code "36") (name "/VCC_VCO") (class "Default")
      (node (ref "C12") (pin "1") (pinfunction "1_1") (pintype "passive"))
      (node (ref "C20") (pin "1") (pinfunction "1_1") (pintype "passive"))
      (node (ref "C21") (pin "1") (pinfunction "1_1") (pintype "passive"))
      (node (ref "C22") (pin "1") (pinfunction "1_1") (pintype "passive"))
      (node (ref "FB3") (pin "2") (pinfunction "2_2") (pintype "passive"))
      (node (ref "U2") (pin "34") (pinfunction "VCC_VCO_34") (pintype "power_in"))
      (node (ref "U2") (pin "35") (pinfunction "VCC_VCO_35") (pintype "power_in"))
    )
    (net (code "37") (name "/VDD") (class "Default")
      (node (ref "C265") (pin "1") (pinfunction "1_1") (pintype "passive"))
      (node (ref "C306") (pin "1") (pinfunction "1_1") (pintype "passive"))
      (node (ref "FB25") (pin "2") (pinfunction "2_2") (pintype "passive"))
      (node (ref "U4") (pin "11") (pinfunction "VDD2_11") (pintype "power_in"))
      (node (ref "U4") (pin "14") (pinfunction "VDD1_2_14") (pintype "power_in"))
      (node (ref "U4") (pin "17") (pinfunction "VDD1_17") (pintype "power_in"))
      (node (ref "U4") (pin "8") (pinfunction "VDD2_2_8") (pintype "power_in"))
    )
    (net (code "38") (name "GND") (class "Default")
      (node (ref "C12") (pin "2") (pinfunction "2_2") (pintype "passive"))
      (node (ref "C15") (pin "2") (pinfunction "2_2") (pintype "passive"))
      (node (ref "C16") (pin "2") (pinfunction "2_2") (pintype "passive"))
      (node (ref "C17") (pin "2") (pinfunction "2_2") (pintype "passive"))
      (node (ref "C18") (pin "2") (pinfunction "2_2") (pintype "passive"))
      (node (ref "C20") (pin "2") (pinfunction "2_2") (pintype "passive"))
      (node (ref "C21") (pin "2") (pinfunction "2_2") (pintype "passive"))
      (node (ref "C22") (pin "2") (pinfunction "2_2") (pintype "passive"))
      (node (ref "C24") (pin "2") (pinfunction "2_2") (pintype "passive"))
      (node (ref "C25") (pin "2") (pinfunction "2_2") (pintype "passive"))
      (node (ref "C26") (pin "2") (pinfunction "2_2") (pintype "passive"))
      (node (ref "C265") (pin "2") (pinfunction "2_2") (pintype "passive"))
      (node (ref "C267") (pin "1") (pinfunction "1_1") (pintype "passive"))
      (node (ref "C268") (pin "1") (pinfunction "1_1") (pintype "passive"))
      (node (ref "C269") (pin "2") (pinfunction "2_2") (pintype "passive"))
      (node (ref "C27") (pin "2") (pinfunction "2_2") (pintype "passive"))
      (node (ref "C270") (pin "2") (pinfunction "2_2") (pintype "passive"))
      (node (ref "C271") (pin "2") (pinfunction "2_2") (pintype "passive"))
      (node (ref "C272") (pin "2") (pinfunction "2_2") (pintype "passive"))
      (node (ref "C273") (pin "2") (pinfunction "2_2") (pintype "passive"))
      (node (ref "C275") (pin "1") (pinfunction "1_1") (pintype "passive"))
      (node (ref "C28") (pin "2") (pinfunction "2_2") (pintype "passive"))
      (node (ref "C29") (pin "2") (pinfunction "2_2") (pintype "passive"))
      (node (ref "C306") (pin "2") (pinfunction "2_2") (pintype "passive"))
      (node (ref "C309") (pin "2") (pinfunction "2_2") (pintype "passive"))
      (node (ref "C31") (pin "2") (pinfunction "2_2") (pintype "passive"))
      (node (ref "C310") (pin "2") (pinfunction "2_2") (pintype "passive"))
      (node (ref "C311") (pin "2") (pinfunction "2_2") (pintype "passive"))
      (node (ref "C312") (pin "2") (pinfunction "2_2") (pintype "passive"))
      (node (ref "C313") (pin "2") (pinfunction "2_2") (pintype "passive"))
      (node (ref "C314") (pin "2") (pinfunction "2_2") (pintype "passive"))
      (node (ref "C315") (pin "2") (pinfunction "2_2") (pintype "passive"))
      (node (ref "C32") (pin "2") (pinfunction "2_2") (pintype "passive"))
      (node (ref "D1") (pin "1") (pinfunction "C_1") (pintype "passive"))
      (node (ref "J25") (pin "2") (pinfunction "MNT_1_2") (pintype "passive"))
      (node (ref "J3") (pin "2") (pinfunction "MNT_1_2") (pintype "passive"))
      (node (ref "J3") (pin "3") (pinfunction "MNT_2_3") (pintype "passive"))
      (node (ref "J5") (pin "2") (pinfunction "2_2") (pintype "passive"))
      (node (ref "J5") (pin "3") (pinfunction "3_3") (pintype "passive"))
      (node (ref "J5") (pin "4") (pinfunction "4_4") (pintype "passive"))
      (node (ref "J5") (pin "5") (pinfunction "5_5") (pintype "passive"))
      (node (ref "P13") (pin "3") (pinfunction "3_3") (pintype "passive"))
      (node (ref "P14") (pin "3") (pinfunction "3_3") (pintype "passive"))
      (node (ref "P15") (pin "3") (pinfunction "3_3") (pintype "passive"))
      (node (ref "P8") (pin "1") (pinfunction "1_1") (pintype "passive"))
      (node (ref "P9") (pin "3") (pinfunction "3_3") (pintype "passive"))
      (node (ref "R112") (pin "1") (pinfunction "1_1") (pintype "passive"))
      (node (ref "R113") (pin "1") (pinfunction "1_1") (pintype "passive"))
      (node (ref "R114") (pin "1") (pinfunction "1_1") (pintype "passive"))
      (node (ref "R115") (pin "1") (pinfunction "1_1") (pintype "passive"))
      (node (ref "R118") (pin "1") (pinfunction "1_1") (pintype "passive"))
      (node (ref "R119") (pin "1") (pinfunction "1_1") (pintype "passive"))
      (node (ref "R126") (pin "2") (pinfunction "2_2") (pintype "passive"))
      (node (ref "R24") (pin "1") (pinfunction "1_1") (pintype "passive"))
      (node (ref "R26") (pin "1") (pinfunction "1_1") (pintype "passive"))
      (node (ref "R27") (pin "1") (pinfunction "1_1") (pintype "passive"))
      (node (ref "R29") (pin "1") (pinfunction "1_1") (pintype "passive"))
      (node (ref "R39") (pin "1") (pinfunction "1_1") (pintype "passive"))
      (node (ref "R53") (pin "1") (pinfunction "1_1") (pintype "passive"))
      (node (ref "R85") (pin "1") (pinfunction "1_1") (pintype "passive"))
      (node (ref "R89") (pin "1") (pinfunction "1_1") (pintype "passive"))
      (node (ref "R90") (pin "1") (pinfunction "1_1") (pintype "passive"))
      (node (ref "R96") (pin "1") (pinfunction "1_1") (pintype "passive"))
      (node (ref "R97") (pin "1") (pinfunction "1_1") (pintype "passive"))
      (node (ref "R98") (pin "1") (pinfunction "1_1") (pintype "passive"))
      (node (ref "U2") (pin "2") (pinfunction "SEC_REF-_2") (pintype "passive"))
      (node (ref "U2") (pin "36") (pinfunction "GND_VCO_36") (pintype "power_in"))
      (node (ref "U2") (pin "43") (pinfunction "AUX_IN_43") (pintype "input"))
      (node (ref "U2") (pin "49") (pinfunction "GND_49") (pintype "power_in"))
      (node (ref "U4") (pin "13") (pinfunction "VSS_13") (pintype "passive"))
      (node (ref "U4") (pin "20") (pinfunction "VDD0_2_20") (pintype "power_in"))
      (node (ref "U4") (pin "23") (pinfunction "VDD0_23") (pintype "power_in"))
      (node (ref "U4") (pin "25") (pinfunction "EP_25") (pintype "passive"))
      (node (ref "U4") (pin "7") (pinfunction "VSS_2_7") (pintype "passive"))
    )
    (net (code "39") (name "Net-(C23-Pad2)") (class "Default")
      (node (ref "C23") (pin "2") (pinfunction "2_2") (pintype "passive"))
      (node (ref "J5") (pin "1") (pinfunction "1_1") (pintype "passive"))
      (node (ref "R27") (pin "2") (pinfunction "2_2") (pintype "passive"))
    )
    (net (code "40") (name "Net-(C30-Pad1)") (class "Default")
      (node (ref "C30") (pin "1") (pinfunction "1_1") (pintype "passive"))
      (node (ref "R30") (pin "2") (pinfunction "2_2") (pintype "passive"))
    )
    (net (code "41") (name "Net-(C275-Pad2)") (class "Default")
      (node (ref "C275") (pin "2") (pinfunction "2_2") (pintype "passive"))
      (node (ref "R91") (pin "1") (pinfunction "1_1") (pintype "passive"))
      (node (ref "R92") (pin "1") (pinfunction "1_1") (pintype "passive"))
      (node (ref "R93") (pin "2") (pinfunction "2_2") (pintype "passive"))
    )
    (net (code "42") (name "Net-(D1-A)") (class "Default")
      (node (ref "D1") (pin "2") (pinfunction "A_2") (pintype "passive"))
      (node (ref "R31") (pin "2") (pinfunction "2_2") (pintype "passive"))
    )
    (net (code "43") (name "Net-(P8-Pad3)") (class "Default")
      (node (ref "P8") (pin "3") (pinfunction "3_3") (pintype "passive"))
      (node (ref "R28") (pin "1") (pinfunction "1_1") (pintype "passive"))
      (node (ref "R29") (pin "2") (pinfunction "2_2") (pintype "passive"))
    )
    (net (code "44") (name "Net-(P9-Pad1)") (class "Default")
      (node (ref "P9") (pin "1") (pinfunction "1_1") (pintype "passive"))
      (node (ref "R84") (pin "1") (pinfunction "1_1") (pintype "passive"))
      (node (ref "R85") (pin "2") (pinfunction "2_2") (pintype "passive"))
    )
    (net (code "45") (name "Net-(P13-Pad1)") (class "Default")
      (node (ref "P13") (pin "1") (pinfunction "1_1") (pintype "passive"))
      (node (ref "R88") (pin "1") (pinfunction "1_1") (pintype "passive"))
      (node (ref "R96") (pin "2") (pinfunction "2_2") (pintype "passive"))
    )
    (net (code "46") (name "Net-(P14-Pad1)") (class "Default")
      (node (ref "P14") (pin "1") (pinfunction "1_1") (pintype "passive"))
      (node (ref "R94") (pin "1") (pinfunction "1_1") (pintype "passive"))
      (node (ref "R97") (pin "2") (pinfunction "2_2") (pintype "passive"))
    )
    (net (code "47") (name "Net-(P15-Pad1)") (class "Default")
      (node (ref "P15") (pin "1") (pinfunction "1_1") (pintype "passive"))
      (node (ref "R95") (pin "1") (pinfunction "1_1") (pintype "passive"))
      (node (ref "R98") (pin "2") (pinfunction "2_2") (pintype "passive"))
    )
    (net (code "48") (name "Net-(U2-EXT_LFN)") (class "Default")
      (node (ref "C30") (pin "2") (pinfunction "2_2") (pintype "passive"))
      (node (ref "C33") (pin "2") (pinfunction "2_2") (pintype "passive"))
      (node (ref "U2") (pin "41") (pinfunction "EXT_LFN_41") (pintype "passive"))
    )
    (net (code "49") (name "Net-(U2-EXT_LFP)") (class "Default")
      (node (ref "C33") (pin "1") (pinfunction "1_1") (pintype "passive"))
      (node (ref "R30") (pin "1") (pinfunction "1_1") (pintype "passive"))
      (node (ref "U2") (pin "40") (pinfunction "EXT_LFP_40") (pintype "passive"))
    )
    (net (code "50") (name "Net-(U2-PLL_LOCK)") (class "Default")
      (node (ref "R31") (pin "1") (pinfunction "1_1") (pintype "passive"))
      (node (ref "U2") (pin "37") (pinfunction "PLL_LOCK_37") (pintype "output"))
    )
    (net (code "51") (name "Net-(U2-REF_SEL)") (class "Default")
      (node (ref "J3") (pin "1") (pinfunction "1_1") (pintype "passive"))
      (node (ref "U2") (pin "31") (pinfunction "REF_SEL_31") (pintype "input"))
    )
    (net (code "52") (name "Net-(U2-REG_CAP1)") (class "Default")
      (node (ref "C267") (pin "2") (pinfunction "2_2") (pintype "passive"))
      (node (ref "U2") (pin "4") (pinfunction "REG_CAP1_4") (pintype "passive"))
    )
    (net (code "53") (name "Net-(U2-REG_CAP2)") (class "Default")
      (node (ref "C268") (pin "2") (pinfunction "2_2") (pintype "passive"))
      (node (ref "U2") (pin "38") (pinfunction "REG_CAP2_38") (pintype "passive"))
    )
    (net (code "54") (name "Net-(U2-SEC_REF+)") (class "Default")
      (node (ref "C14") (pin "2") (pinfunction "2_2") (pintype "passive"))
      (node (ref "R23") (pin "1") (pinfunction "1_1") (pintype "passive"))
      (node (ref "R24") (pin "2") (pinfunction "2_2") (pintype "passive"))
      (node (ref "U2") (pin "3") (pinfunction "SEC_REF+_3") (pintype "passive"))
    )
    (net (code "55") (name "Net-(U4-IN)") (class "Default")
      (node (ref "C274") (pin "2") (pinfunction "2_2") (pintype "passive"))
      (node (ref "R91") (pin "2") (pinfunction "2_2") (pintype "passive"))
      (node (ref "U4") (pin "3") (pinfunction "IN_3") (pintype "input"))
    )
    (net (code "56") (name "Net-(U4-~{IN})") (class "Default")
      (node (ref "C276") (pin "2") (pinfunction "2_2") (pintype "passive"))
      (node (ref "R93") (pin "1") (pinfunction "1_1") (pintype "passive"))
      (node (ref "U4") (pin "4") (pinfunction "~{IN}_4") (pintype "input"))
    )
    (net (code "57") (name "Net-(Y1-GND{slash}Case)") (class "Default")
      (node (ref "C13") (pin "2") (pinfunction "2_2") (pintype "passive"))
      (node (ref "Y1") (pin "2") (pinfunction "GND/Case_2") (pintype "power_in"))
    )
    (net (code "58") (name "Net-(Y1-Output)") (class "Default")
      (node (ref "C13") (pin "1") (pinfunction "1_1") (pintype "passive"))
      (node (ref "C14") (pin "1") (pinfunction "1_1") (pintype "passive"))
      (node (ref "Y1") (pin "3") (pinfunction "Output_3") (pintype "output"))
    )
    (net (code "59") (name "Net-(Y1-~{STBY})") (class "Default")
      (node (ref "P2") (pin "1") (pinfunction "1_1") (pintype "passive"))
      (node (ref "Y1") (pin "1") (pinfunction "~{STBY}_1") (pintype "input"))
    )
    (net (code "60") (name "unconnected-(U2-AUX_OUT-Pad13)") (class "Default")
      (node (ref "U2") (pin "13") (pinfunction "AUX_OUT_13") (pintype "output"))
    )
    (net (code "61") (name "unconnected-(U4-NC-Pad12)") (class "Default")
      (node (ref "U4") (pin "12") (pinfunction "NC_12") (pintype "passive"))
    )
    (net (code "62") (name "unconnected-(U4-Y0-Pad21)") (class "Default")
      (node (ref "U4") (pin "21") (pinfunction "Y0_21") (pintype "output"))
    )
    (net (code "63") (name "unconnected-(U4-~{Y0}-Pad22)") (class "Default")
      (node (ref "U4") (pin "22") (pinfunction "~{Y0}_22") (pintype "output"))
    )
  )
)
